# mpc56_cwconn.net
KiCad netlist of a schematic drawn in Altium Designer
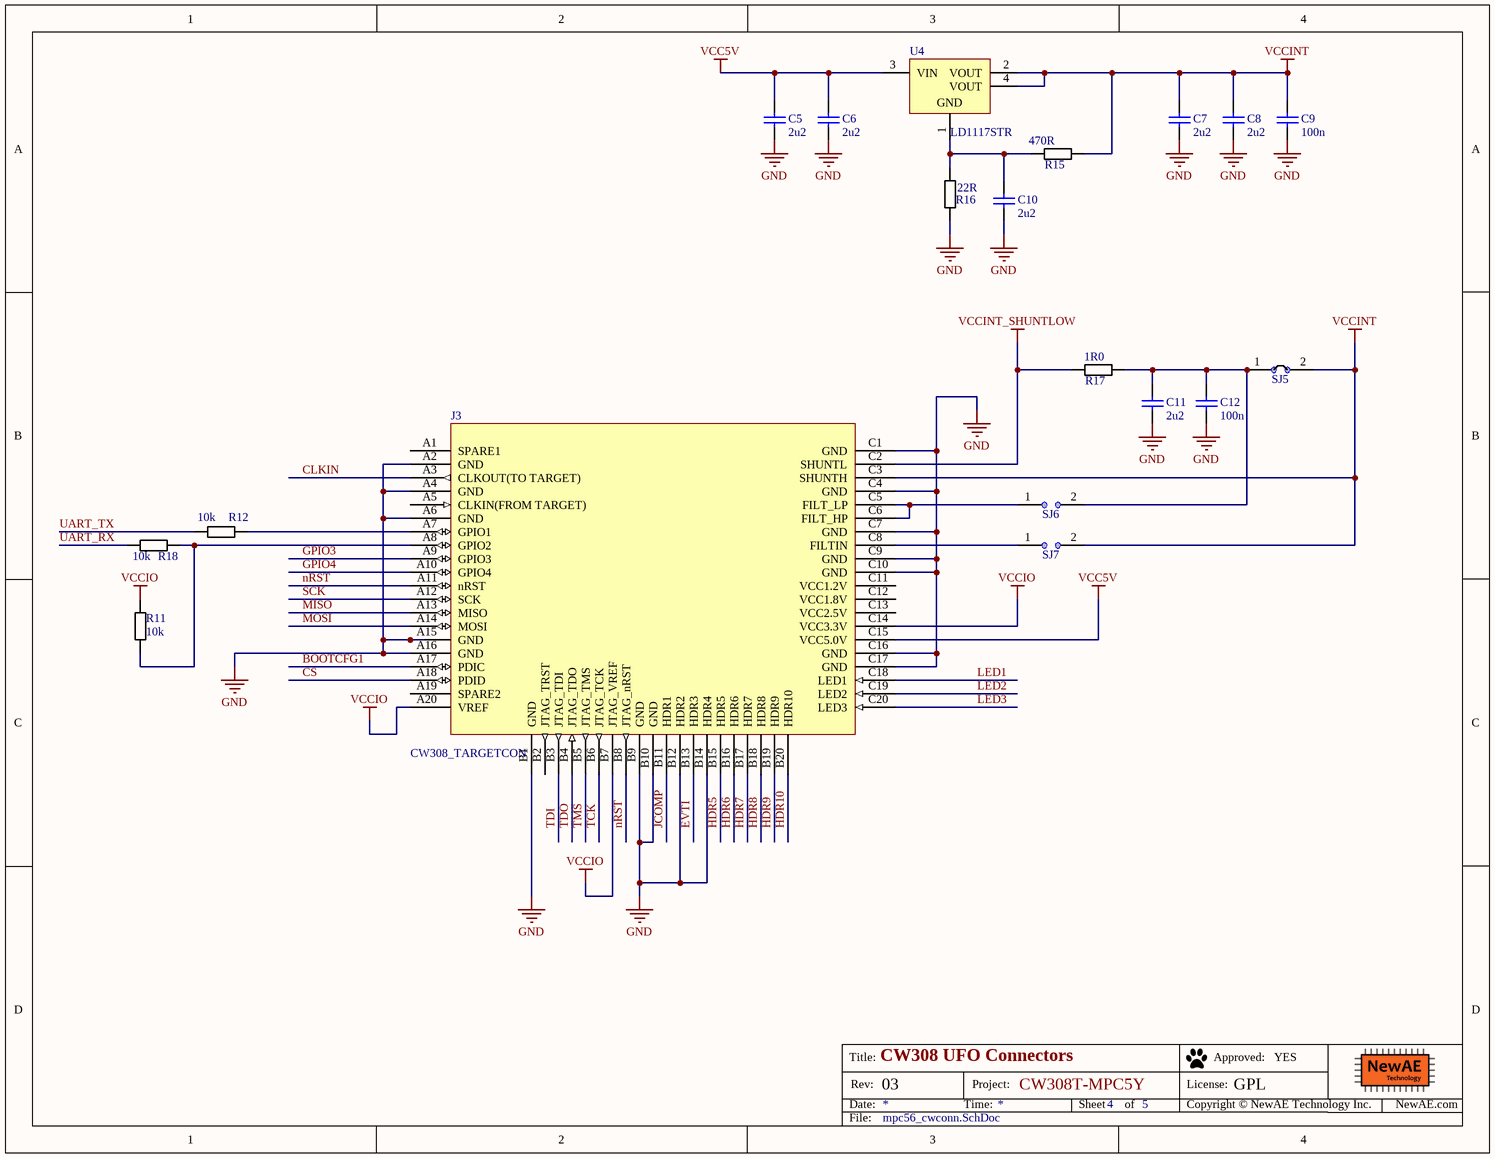
[diagram p0: mpc56_cwconn.SchDoc]

(export (version "E")
  (design (tool "Eeschema 10.0.6"))
  (components
    (comp (ref "C5")
      (value "2u2")
      (footprint "CAPC0603_M")
      (description "2u2, 0603")
      (fields (field (name "PART NUMBER") "CCHIP-2u2-0603"))
      (libsource (lib "NewAE_AltiumLib") (part "CAP"))
    )
    (comp (ref "C6")
      (value "2u2")
      (footprint "CAPC0603_M")
      (description "2u2, 0603")
      (fields (field (name "PART NUMBER") "CCHIP-2u2-0603"))
      (libsource (lib "NewAE_AltiumLib") (part "CAP"))
    )
    (comp (ref "C7")
      (value "2u2")
      (footprint "CAPC0603_M")
      (description "2u2, 0603")
      (fields (field (name "PART NUMBER") "CCHIP-2u2-0603"))
      (libsource (lib "NewAE_AltiumLib") (part "CAP"))
    )
    (comp (ref "C8")
      (value "2u2")
      (footprint "CAPC0603_M")
      (description "2u2, 0603")
      (fields (field (name "PART NUMBER") "CCHIP-2u2-0603"))
      (libsource (lib "NewAE_AltiumLib") (part "CAP"))
    )
    (comp (ref "C9")
      (value "100n")
      (footprint "CAPC0402_M")
      (description "100n, 0402")
      (fields (field (name "PART NUMBER") "CCHIP-100n-0402"))
      (libsource (lib "NewAE_AltiumLib") (part "CAP"))
    )
    (comp (ref "C10")
      (value "2u2")
      (footprint "CAPC0603_M")
      (description "2u2, 0603")
      (fields (field (name "PART NUMBER") "CCHIP-2u2-0603"))
      (libsource (lib "NewAE_AltiumLib") (part "CAP"))
    )
    (comp (ref "C11")
      (value "2u2")
      (footprint "CAPC0603_M")
      (description "2u2, 0603")
      (fields (field (name "PART NUMBER") "CCHIP-2u2-0603"))
      (libsource (lib "NewAE_AltiumLib") (part "CAP"))
    )
    (comp (ref "C12")
      (value "100n")
      (footprint "CAPC0402_M")
      (description "100n, 0402")
      (fields (field (name "PART NUMBER") "CCHIP-100n-0402"))
      (libsource (lib "NewAE_AltiumLib") (part "CAP"))
    )
    (comp (ref "J3")
      (value "CW308_TARGETCON")
      (footprint "ChipWhisperer_AltiumLib:CW308_TBOARD_CONN")
      (description "CW308 \"Standard\" Target Board Connector")
      (libsource (lib "ChipWhisperer_AltiumLib") (part "CW308_TBOARD"))
    )
    (comp (ref "R11")
      (value "10k")
      (footprint "RESC1608X55N")
      (description "10k res, 0603, 1%, 1/10W")
      (fields (field (name "PART NUMBER") "RCHIP-10K-0603") (field (name "TOLERANCE") "1%"))
      (libsource (lib "") (part "RES-EU_3"))
    )
    (comp (ref "R12")
      (value "10k")
      (footprint "RESC1608X55N")
      (description "10k res, 0603, 1%, 1/10W")
      (fields (field (name "PART NUMBER") "RCHIP-10K-0603") (field (name "TOLERANCE") "1%"))
      (libsource (lib "") (part "RES-EU_2"))
    )
    (comp (ref "R15")
      (value "470R")
      (footprint "RESC1608X55N")
      (description "470R res, 0603, 1%, 1/10W")
      (fields (field (name "PART NUMBER") "RCHIP-120R-0603") (field (name "TOLERANCE") "1%"))
      (libsource (lib "NewAE_AltiumLib") (part "RES-EU"))
    )
    (comp (ref "R16")
      (value "22R")
      (footprint "RESC1608X55N")
      (description "120R res, 0603, 1%, 1/10W")
      (fields (field (name "PART NUMBER") "RCHIP-120R-0603") (field (name "TOLERANCE") "1%"))
      (libsource (lib "") (part "RES-EU_1"))
    )
    (comp (ref "R17")
      (value "1R0")
      (footprint "RESC2012X70N")
      (description "1R0 res, 0805, 1%, 1/8W")
      (fields (field (name "PART NUMBER") "RCHIP-1R0-0805") (field (name "TOLERANCE") "1%"))
      (libsource (lib "") (part "RES-EU_2"))
    )
    (comp (ref "R18")
      (value "10k")
      (footprint "RESC1608X55N")
      (description "10k res, 0603, 1%, 1/10W")
      (fields (field (name "PART NUMBER") "RCHIP-10K-0603") (field (name "TOLERANCE") "1%"))
      (libsource (lib "") (part "RES-EU_2"))
    )
    (comp (ref "SJ5")
      (value "NC")
      (footprint "SJ_2S_NC")
      (description "Solder Jumper, NC")
      (fields (field (name "PART NUMBER") "SJ_2S"))
      (libsource (lib "NewAE_AltiumLib") (part "SJ_2S"))
    )
    (comp (ref "SJ6")
      (value "NO")
      (footprint "SJ_2S_NO")
      (description "Solder Jumper, NO")
      (fields (field (name "PART NUMBER") "SJ_2S_NO"))
      (libsource (lib "NewAE_AltiumLib") (part "SJ_2S_NO"))
    )
    (comp (ref "SJ7")
      (value "NO")
      (footprint "SJ_2S_NO")
      (description "Solder Jumper, NO")
      (fields (field (name "PART NUMBER") "SJ_2S_NO"))
      (libsource (lib "NewAE_AltiumLib") (part "SJ_2S_NO"))
    )
    (comp (ref "U4")
      (value "LD1117STR")
      (footprint "SOT-223_L")
      (description "Adjustable Low Drop Voltage Regulator, 1.25 to 15V, 4-Pin SOT-223, Tape and Reel")
      (libsource (lib "Altium Content Vault") (part "CMP-0244-00313-1"))
    )
  )
  (nets
    (net (code "1") (name "/BOOTCFG1") (class "Default")
      (node (ref "J3") (pin "A17") (pinfunction "PDIC_A17") (pintype "bidirectional"))
    )
    (net (code "2") (name "/CLKIN") (class "Default")
      (node (ref "J3") (pin "A3") (pinfunction "CLKOUT(TO_TARGET)_A3") (pintype "output"))
    )
    (net (code "3") (name "/CS") (class "Default")
      (node (ref "J3") (pin "A18") (pinfunction "PDID_A18") (pintype "bidirectional"))
    )
    (net (code "4") (name "/EVTI") (class "Default")
      (node (ref "J3") (pin "B13") (pinfunction "HDR3_B13") (pintype "passive"))
    )
    (net (code "5") (name "/GPIO3") (class "Default")
      (node (ref "J3") (pin "A9") (pinfunction "GPIO3_A9") (pintype "bidirectional"))
    )
    (net (code "6") (name "/GPIO4") (class "Default")
      (node (ref "J3") (pin "A10") (pinfunction "GPIO4_A10") (pintype "bidirectional"))
    )
    (net (code "7") (name "/HDR5") (class "Default")
      (node (ref "J3") (pin "B15") (pinfunction "HDR5_B15") (pintype "passive"))
    )
    (net (code "8") (name "/HDR6") (class "Default")
      (node (ref "J3") (pin "B16") (pinfunction "HDR6_B16") (pintype "passive"))
    )
    (net (code "9") (name "/HDR7") (class "Default")
      (node (ref "J3") (pin "B17") (pinfunction "HDR7_B17") (pintype "passive"))
    )
    (net (code "10") (name "/HDR8") (class "Default")
      (node (ref "J3") (pin "B18") (pinfunction "HDR8_B18") (pintype "passive"))
    )
    (net (code "11") (name "/HDR9") (class "Default")
      (node (ref "J3") (pin "B19") (pinfunction "HDR9_B19") (pintype "passive"))
    )
    (net (code "12") (name "/HDR10") (class "Default")
      (node (ref "J3") (pin "B20") (pinfunction "HDR10_B20") (pintype "passive"))
    )
    (net (code "13") (name "/JCOMP") (class "Default")
      (node (ref "J3") (pin "B11") (pinfunction "HDR1_B11") (pintype "passive"))
    )
    (net (code "14") (name "/LED1") (class "Default")
      (node (ref "J3") (pin "C18") (pinfunction "LED1_C18") (pintype "input"))
    )
    (net (code "15") (name "/LED2") (class "Default")
      (node (ref "J3") (pin "C19") (pinfunction "LED2_C19") (pintype "input"))
    )
    (net (code "16") (name "/LED3") (class "Default")
      (node (ref "J3") (pin "C20") (pinfunction "LED3_C20") (pintype "input"))
    )
    (net (code "17") (name "/MISO") (class "Default")
      (node (ref "J3") (pin "A13") (pinfunction "MISO_A13") (pintype "bidirectional"))
    )
    (net (code "18") (name "/MOSI") (class "Default")
      (node (ref "J3") (pin "A14") (pinfunction "MOSI_A14") (pintype "bidirectional"))
    )
    (net (code "19") (name "/SCK") (class "Default")
      (node (ref "J3") (pin "A12") (pinfunction "SCK_A12") (pintype "bidirectional"))
    )
    (net (code "20") (name "/TCK") (class "Default")
      (node (ref "J3") (pin "B6") (pinfunction "JTAG_TCK_B6") (pintype "output"))
    )
    (net (code "21") (name "/TDI") (class "Default")
      (node (ref "J3") (pin "B3") (pinfunction "JTAG_TDI_B3") (pintype "output"))
    )
    (net (code "22") (name "/TDO") (class "Default")
      (node (ref "J3") (pin "B4") (pinfunction "JTAG_TDO_B4") (pintype "input"))
    )
    (net (code "23") (name "/TMS") (class "Default")
      (node (ref "J3") (pin "B5") (pinfunction "JTAG_TMS_B5") (pintype "output"))
    )
    (net (code "24") (name "/UART_RX") (class "Default")
      (node (ref "R18") (pin "1") (pinfunction "1_1") (pintype "passive"))
    )
    (net (code "25") (name "/UART_TX") (class "Default")
      (node (ref "R12") (pin "1") (pinfunction "1_1") (pintype "passive"))
    )
    (net (code "26") (name "/nRST") (class "Default")
      (node (ref "J3") (pin "A11") (pinfunction "nRST_A11") (pintype "bidirectional"))
      (node (ref "J3") (pin "B8") (pinfunction "JTAG_nRST_B8") (pintype "output"))
    )
    (net (code "27") (name "GND") (class "Default")
      (node (ref "C10") (pin "2") (pinfunction "2_2") (pintype "passive"))
      (node (ref "C11") (pin "2") (pinfunction "2_2") (pintype "passive"))
      (node (ref "C12") (pin "2") (pinfunction "2_2") (pintype "passive"))
      (node (ref "C5") (pin "2") (pinfunction "2_2") (pintype "passive"))
      (node (ref "C6") (pin "2") (pinfunction "2_2") (pintype "passive"))
      (node (ref "C7") (pin "2") (pinfunction "2_2") (pintype "passive"))
      (node (ref "C8") (pin "2") (pinfunction "2_2") (pintype "passive"))
      (node (ref "C9") (pin "2") (pinfunction "2_2") (pintype "passive"))
      (node (ref "J3") (pin "A15") (pinfunction "GND_A15") (pintype "passive"))
      (node (ref "J3") (pin "A16") (pinfunction "GND_A16") (pintype "passive"))
      (node (ref "J3") (pin "A2") (pinfunction "GND_A2") (pintype "passive"))
      (node (ref "J3") (pin "A4") (pinfunction "GND_A4") (pintype "passive"))
      (node (ref "J3") (pin "A6") (pinfunction "GND_A6") (pintype "power_in"))
      (node (ref "J3") (pin "B1") (pinfunction "GND_B1") (pintype "passive"))
      (node (ref "J3") (pin "B10") (pinfunction "GND_B10") (pintype "passive"))
      (node (ref "J3") (pin "B12") (pinfunction "HDR2_B12") (pintype "passive"))
      (node (ref "J3") (pin "B14") (pinfunction "HDR4_B14") (pintype "passive"))
      (node (ref "J3") (pin "B9") (pinfunction "GND_B9") (pintype "passive"))
      (node (ref "J3") (pin "C1") (pinfunction "GND_C1") (pintype "power_in"))
      (node (ref "J3") (pin "C10") (pinfunction "GND_C10") (pintype "power_in"))
      (node (ref "J3") (pin "C16") (pinfunction "GND_C16") (pintype "power_in"))
      (node (ref "J3") (pin "C17") (pinfunction "GND_C17") (pintype "power_in"))
      (node (ref "J3") (pin "C4") (pinfunction "GND_C4") (pintype "power_in"))
      (node (ref "J3") (pin "C7") (pinfunction "GND_C7") (pintype "power_in"))
      (node (ref "J3") (pin "C9") (pinfunction "GND_C9") (pintype "power_in"))
      (node (ref "R16") (pin "2") (pinfunction "2_2") (pintype "passive"))
    )
    (net (code "28") (name "Net-(C11-Pad1)") (class "Default")
      (node (ref "C11") (pin "1") (pinfunction "1_1") (pintype "passive"))
      (node (ref "C12") (pin "1") (pinfunction "1_1") (pintype "passive"))
      (node (ref "R17") (pin "2") (pinfunction "2_2") (pintype "passive"))
      (node (ref "SJ5") (pin "1") (pinfunction "1_1") (pintype "passive"))
      (node (ref "SJ6") (pin "2") (pinfunction "2_2") (pintype "passive"))
    )
    (net (code "29") (name "Net-(J3-FILTIN)") (class "Default")
      (node (ref "J3") (pin "C8") (pinfunction "FILTIN_C8") (pintype "passive"))
      (node (ref "SJ7") (pin "1") (pinfunction "1_1") (pintype "passive"))
    )
    (net (code "30") (name "Net-(J3-FILT_HP)") (class "Default")
      (node (ref "J3") (pin "C5") (pinfunction "FILT_LP_C5") (pintype "passive"))
      (node (ref "J3") (pin "C6") (pinfunction "FILT_HP_C6") (pintype "passive"))
      (node (ref "SJ6") (pin "1") (pinfunction "1_1") (pintype "passive"))
    )
    (net (code "31") (name "Net-(J3-GPIO1)") (class "Default")
      (node (ref "J3") (pin "A7") (pinfunction "GPIO1_A7") (pintype "bidirectional"))
      (node (ref "R12") (pin "2") (pinfunction "2_2") (pintype "passive"))
    )
    (net (code "32") (name "Net-(J3-GPIO2)") (class "Default")
      (node (ref "J3") (pin "A8") (pinfunction "GPIO2_A8") (pintype "bidirectional"))
      (node (ref "R11") (pin "1") (pinfunction "1_1") (pintype "passive"))
      (node (ref "R18") (pin "2") (pinfunction "2_2") (pintype "passive"))
    )
    (net (code "33") (name "Net-(U4-GND)") (class "Default")
      (node (ref "C10") (pin "1") (pinfunction "1_1") (pintype "passive"))
      (node (ref "R15") (pin "2") (pinfunction "2_2") (pintype "passive"))
      (node (ref "R16") (pin "1") (pinfunction "1_1") (pintype "passive"))
      (node (ref "U4") (pin "1") (pinfunction "GND_1") (pintype "power_in"))
    )
    (net (code "34") (name "VCC5V") (class "Default")
      (node (ref "C5") (pin "1") (pinfunction "1_1") (pintype "passive"))
      (node (ref "C6") (pin "1") (pinfunction "1_1") (pintype "passive"))
      (node (ref "J3") (pin "C15") (pinfunction "VCC5.0V_C15") (pintype "power_in"))
      (node (ref "U4") (pin "3") (pinfunction "VIN_3") (pintype "power_in"))
    )
    (net (code "35") (name "VCCINT") (class "Default")
      (node (ref "C7") (pin "1") (pinfunction "1_1") (pintype "passive"))
      (node (ref "C8") (pin "1") (pinfunction "1_1") (pintype "passive"))
      (node (ref "C9") (pin "1") (pinfunction "1_1") (pintype "passive"))
      (node (ref "J3") (pin "C3") (pinfunction "SHUNTH_C3") (pintype "passive"))
      (node (ref "R15") (pin "1") (pinfunction "1_1") (pintype "passive"))
      (node (ref "SJ5") (pin "2") (pinfunction "2_2") (pintype "passive"))
      (node (ref "SJ7") (pin "2") (pinfunction "2_2") (pintype "passive"))
      (node (ref "U4") (pin "2") (pinfunction "VOUT_2") (pintype "power_in"))
      (node (ref "U4") (pin "4") (pinfunction "VOUT_4") (pintype "power_in"))
    )
    (net (code "36") (name "VCCINT_SHUNTLOW") (class "Default")
      (node (ref "J3") (pin "C2") (pinfunction "SHUNTL_C2") (pintype "passive"))
      (node (ref "R17") (pin "1") (pinfunction "1_1") (pintype "passive"))
    )
    (net (code "37") (name "VCCIO") (class "Default")
      (node (ref "J3") (pin "A20") (pinfunction "VREF_A20") (pintype "tri_state"))
      (node (ref "J3") (pin "B7") (pinfunction "JTAG_VREF_B7") (pintype "tri_state"))
      (node (ref "J3") (pin "C14") (pinfunction "VCC3.3V_C14") (pintype "power_in"))
      (node (ref "R11") (pin "2") (pinfunction "2_2") (pintype "passive"))
    )
    (net (code "38") (name "unconnected-(J3-CLKIN(FROM_TARGET)-PadA5)") (class "Default")
      (node (ref "J3") (pin "A5") (pinfunction "CLKIN(FROM_TARGET)_A5") (pintype "input"))
    )
    (net (code "39") (name "unconnected-(J3-JTAG_TRST-PadB2)") (class "Default")
      (node (ref "J3") (pin "B2") (pinfunction "JTAG_TRST_B2") (pintype "output"))
    )
    (net (code "40") (name "unconnected-(J3-SPARE1-PadA1)") (class "Default")
      (node (ref "J3") (pin "A1") (pinfunction "SPARE1_A1") (pintype "passive"))
    )
    (net (code "41") (name "unconnected-(J3-SPARE2-PadA19)") (class "Default")
      (node (ref "J3") (pin "A19") (pinfunction "SPARE2_A19") (pintype "passive"))
    )
    (net (code "42") (name "unconnected-(J3-VCC1.2V-PadC11)") (class "Default")
      (node (ref "J3") (pin "C11") (pinfunction "VCC1.2V_C11") (pintype "power_in"))
    )
    (net (code "43") (name "unconnected-(J3-VCC1.8V-PadC12)") (class "Default")
      (node (ref "J3") (pin "C12") (pinfunction "VCC1.8V_C12") (pintype "power_in"))
    )
    (net (code "44") (name "unconnected-(J3-VCC2.5V-PadC13)") (class "Default")
      (node (ref "J3") (pin "C13") (pinfunction "VCC2.5V_C13") (pintype "power_in"))
    )
  )
)
